# TX_FM.net
KiCad netlist of a schematic drawn in Altium Designer
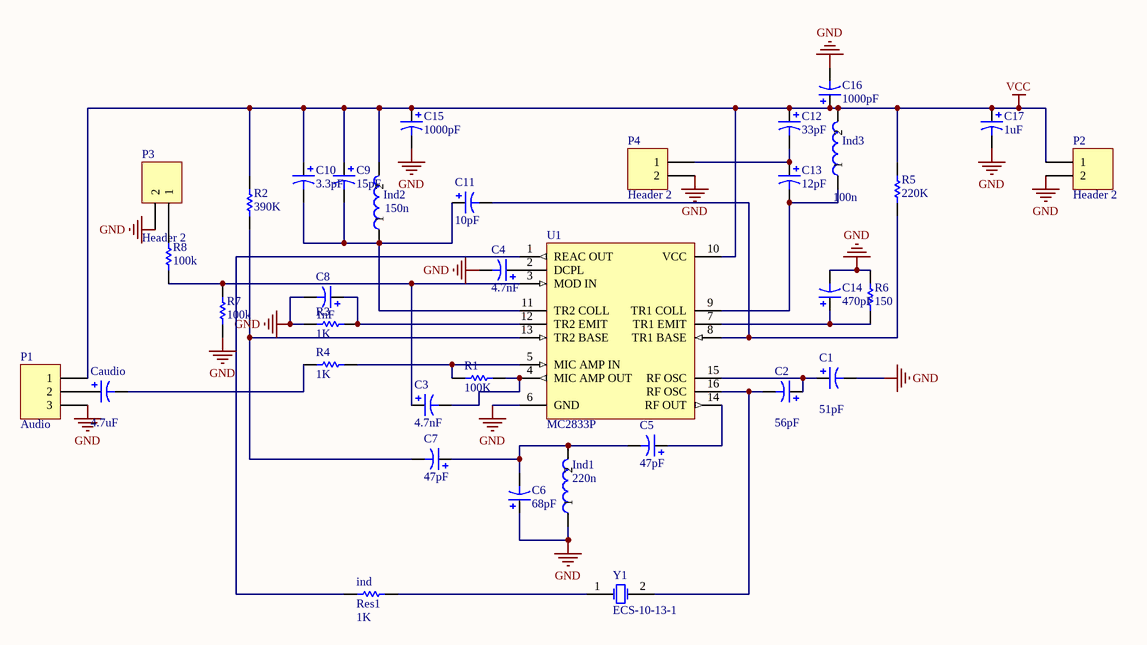
[diagram p0: TX_FM.SchDoc]

(export (version "E")
  (design (tool "Eeschema 10.0.6"))
  (components
    (comp (ref "C1")
      (value "51pF")
      (footprint "C0805")
      (description "Polarized Capacitor (Surface Mount)")
      (fields (field (name "Comment") "Cap Pol3") (field (name "PUBLISHER") "Altium Limited"))
      (libsource (lib "Miscellaneous Devices") (part "Cap Pol3"))
    )
    (comp (ref "C2")
      (value "56pF")
      (footprint "C0805")
      (description "Polarized Capacitor (Surface Mount)")
      (fields (field (name "Comment") "Cap Pol3") (field (name "PUBLISHER") "Altium Limited"))
      (libsource (lib "Miscellaneous Devices") (part "Cap Pol3"))
    )
    (comp (ref "C3")
      (value "4.7nF")
      (footprint "C0805")
      (description "Polarized Capacitor (Surface Mount)")
      (fields (field (name "Comment") "Cap Pol3") (field (name "PUBLISHER") "Altium Limited"))
      (libsource (lib "Miscellaneous Devices") (part "Cap Pol3"))
    )
    (comp (ref "C4")
      (value "4.7nF")
      (footprint "C0805")
      (description "Polarized Capacitor (Surface Mount)")
      (fields (field (name "Comment") "Cap Pol3") (field (name "PUBLISHER") "Altium Limited"))
      (libsource (lib "Miscellaneous Devices") (part "Cap Pol3"))
    )
    (comp (ref "C5")
      (value "47pF")
      (footprint "C0805")
      (description "Polarized Capacitor (Surface Mount)")
      (fields (field (name "Comment") "Cap Pol3") (field (name "PUBLISHER") "Altium Limited"))
      (libsource (lib "Miscellaneous Devices") (part "Cap Pol3"))
    )
    (comp (ref "C6")
      (value "68pF")
      (footprint "C0805")
      (description "Polarized Capacitor (Surface Mount)")
      (fields (field (name "Comment") "Cap Pol3") (field (name "PUBLISHER") "Altium Limited"))
      (libsource (lib "Miscellaneous Devices") (part "Cap Pol3"))
    )
    (comp (ref "C7")
      (value "47pF")
      (footprint "C0805")
      (description "Polarized Capacitor (Surface Mount)")
      (fields (field (name "Comment") "Cap Pol3") (field (name "PUBLISHER") "Altium Limited"))
      (libsource (lib "Miscellaneous Devices") (part "Cap Pol3"))
    )
    (comp (ref "C8")
      (value "1nF")
      (footprint "C0805")
      (description "Polarized Capacitor (Surface Mount)")
      (fields (field (name "Comment") "Cap Pol3") (field (name "PUBLISHER") "Altium Limited"))
      (libsource (lib "Miscellaneous Devices") (part "Cap Pol3"))
    )
    (comp (ref "C9")
      (value "15pF")
      (footprint "C0805")
      (description "Polarized Capacitor (Surface Mount)")
      (fields (field (name "Comment") "Cap Pol3") (field (name "PUBLISHER") "Altium Limited"))
      (libsource (lib "Miscellaneous Devices") (part "Cap Pol3"))
    )
    (comp (ref "C10")
      (value "3.3pF")
      (footprint "C0805")
      (description "Polarized Capacitor (Surface Mount)")
      (fields (field (name "Comment") "Cap Pol3") (field (name "PUBLISHER") "Altium Limited"))
      (libsource (lib "Miscellaneous Devices") (part "Cap Pol3"))
    )
    (comp (ref "C11")
      (value "10pF")
      (footprint "C0805")
      (description "Polarized Capacitor (Surface Mount)")
      (fields (field (name "Comment") "Cap Pol3") (field (name "PUBLISHER") "Altium Limited"))
      (libsource (lib "Miscellaneous Devices") (part "Cap Pol3"))
    )
    (comp (ref "C12")
      (value "33pF")
      (footprint "C0805")
      (description "Polarized Capacitor (Surface Mount)")
      (fields (field (name "Comment") "Cap Pol3") (field (name "PUBLISHER") "Altium Limited"))
      (libsource (lib "Miscellaneous Devices") (part "Cap Pol3"))
    )
    (comp (ref "C13")
      (value "12pF")
      (footprint "C0805")
      (description "Polarized Capacitor (Surface Mount)")
      (fields (field (name "Comment") "Cap Pol3") (field (name "PUBLISHER") "Altium Limited"))
      (libsource (lib "Miscellaneous Devices") (part "Cap Pol3"))
    )
    (comp (ref "C14")
      (value "470pF")
      (footprint "C0805")
      (description "Polarized Capacitor (Surface Mount)")
      (fields (field (name "Comment") "Cap Pol3") (field (name "PUBLISHER") "Altium Limited"))
      (libsource (lib "Miscellaneous Devices") (part "Cap Pol3"))
    )
    (comp (ref "C15")
      (value "1000pF")
      (footprint "C0805")
      (description "Polarized Capacitor (Surface Mount)")
      (fields (field (name "Comment") "Cap Pol3") (field (name "PUBLISHER") "Altium Limited"))
      (libsource (lib "Miscellaneous Devices") (part "Cap Pol3"))
    )
    (comp (ref "C16")
      (value "1000pF")
      (footprint "C0805")
      (description "Polarized Capacitor (Surface Mount)")
      (fields (field (name "Comment") "Cap Pol3") (field (name "PUBLISHER") "Altium Limited"))
      (libsource (lib "Miscellaneous Devices") (part "Cap Pol3"))
    )
    (comp (ref "C17")
      (value "1uF")
      (footprint "C0805")
      (description "Polarized Capacitor (Surface Mount)")
      (fields (field (name "Comment") "Cap Pol3") (field (name "PUBLISHER") "Altium Limited"))
      (libsource (lib "Miscellaneous Devices") (part "Cap Pol3"))
    )
    (comp (ref "Caudio")
      (value "4.7uF")
      (footprint "B")
      (description "Polarized Capacitor (Radial)")
      (fields (field (name "Comment") "Cap Pol1") (field (name "PUBLISHER") "Altium Limited"))
      (libsource (lib "Miscellaneous Devices") (part "Cap Pol1"))
    )
    (comp (ref "ind")
      (value "Res1")
      (footprint "AXIAL-0.3")
      (description "Resistor")
      (fields (field (name "ALTIUM_VALUE") "1K") (field (name "PUBLISHER") "Altium Limited"))
      (libsource (lib "Miscellaneous Devices") (part "Res1"))
    )
    (comp (ref "Ind1")
      (value "Ind2")
      (footprint "IND_7MM")
      (fields (field (name "VALOR") "220n"))
      (libsource (lib "epf") (part "Ind2"))
    )
    (comp (ref "Ind2")
      (value "Ind2")
      (footprint "Ind_5mm")
      (fields (field (name "VALOR") "150n"))
      (libsource (lib "epf") (part "Ind2"))
    )
    (comp (ref "Ind3")
      (value "Ind2")
      (footprint "Ind_5mm")
      (fields (field (name "VALOR") "100n"))
      (libsource (lib "epf") (part "Ind2"))
    )
    (comp (ref "P1")
      (value "Audio")
      (footprint "HDR1X3")
      (description "Header, 3-Pin")
      (fields (field (name "PUBLISHER") "Altium Limited"))
      (libsource (lib "Miscellaneous Connectors") (part "Header 3"))
    )
    (comp (ref "P2")
      (value "Header 2")
      (footprint "HDR1X2")
      (description "Header, 2-Pin")
      (fields (field (name "PUBLISHER") "Altium Limited"))
      (libsource (lib "Miscellaneous Connectors") (part "Header 2"))
    )
    (comp (ref "P3")
      (value "Header 2")
      (footprint "HDR1X2")
      (description "Header, 2-Pin")
      (fields (field (name "PUBLISHER") "Altium Limited"))
      (libsource (lib "") (part "Header 2_2"))
    )
    (comp (ref "P4")
      (value "Header 2")
      (footprint "HDR1X2")
      (description "Header, 2-Pin")
      (fields (field (name "PUBLISHER") "Altium Limited"))
      (libsource (lib "") (part "Header 2_1"))
    )
    (comp (ref "R1")
      (value "100K")
      (footprint "2012[0805]")
      (description "Semiconductor Resistor")
      (fields (field (name "Comment") "Res Semi") (field (name "PUBLISHER") "Altium Limited"))
      (libsource (lib "Miscellaneous Devices") (part "Res Semi"))
    )
    (comp (ref "R2")
      (value "390K")
      (footprint "2012[0805]")
      (description "Semiconductor Resistor")
      (fields (field (name "Comment") "Res Semi") (field (name "PUBLISHER") "Altium Limited"))
      (libsource (lib "Miscellaneous Devices") (part "Res Semi"))
    )
    (comp (ref "R3")
      (value "1K")
      (footprint "2012[0805]")
      (description "Semiconductor Resistor")
      (fields (field (name "Comment") "Res Semi") (field (name "PUBLISHER") "Altium Limited"))
      (libsource (lib "Miscellaneous Devices") (part "Res Semi"))
    )
    (comp (ref "R4")
      (value "1K")
      (footprint "2012[0805]")
      (description "Semiconductor Resistor")
      (fields (field (name "Comment") "Res Semi") (field (name "PUBLISHER") "Altium Limited"))
      (libsource (lib "Miscellaneous Devices") (part "Res Semi"))
    )
    (comp (ref "R5")
      (value "220K")
      (footprint "2012[0805]")
      (description "Semiconductor Resistor")
      (fields (field (name "Comment") "Res Semi") (field (name "PUBLISHER") "Altium Limited"))
      (libsource (lib "Miscellaneous Devices") (part "Res Semi"))
    )
    (comp (ref "R6")
      (value "150")
      (footprint "2012[0805]")
      (description "Semiconductor Resistor")
      (fields (field (name "Comment") "Res Semi") (field (name "PUBLISHER") "Altium Limited"))
      (libsource (lib "Miscellaneous Devices") (part "Res Semi"))
    )
    (comp (ref "R7")
      (value "100k")
      (footprint "2012[0805]")
      (description "Semiconductor Resistor")
      (fields (field (name "Comment") "Res Semi") (field (name "PUBLISHER") "Altium Limited"))
      (libsource (lib "Miscellaneous Devices") (part "Res Semi"))
    )
    (comp (ref "R8")
      (value "100k")
      (footprint "2012[0805]")
      (description "Semiconductor Resistor")
      (fields (field (name "Comment") "Res Semi") (field (name "PUBLISHER") "Altium Limited"))
      (libsource (lib "Miscellaneous Devices") (part "Res Semi"))
    )
    (comp (ref "U1")
      (value "MC2833P")
      (footprint "648-06")
      (description "Low Power FM Transmitter System")
      (fields (field (name "PUBLISHER") "Altium Limited"))
      (libsource (lib "Motorola RF and IF Transmitter") (part "MC2833P"))
    )
    (comp (ref "Y1")
      (value "ECS-10-13-1")
      (footprint "HC-49U")
      (description "Crystal Oscillator")
      (fields (field (name "PUBLISHER") "Altium Limited"))
      (libsource (lib "ECS Crystal Oscillator") (part "ECS-10-13-1"))
    )
  )
  (nets
    (net (code "1") (name "GND") (class "Default")
      (node (ref "C1") (pin "2") (pinfunction "2_2") (pintype "passive"))
      (node (ref "C14") (pin "2") (pinfunction "2_2") (pintype "passive"))
      (node (ref "C15") (pin "2") (pinfunction "2_2") (pintype "passive"))
      (node (ref "C16") (pin "2") (pinfunction "2_2") (pintype "passive"))
      (node (ref "C17") (pin "2") (pinfunction "2_2") (pintype "passive"))
      (node (ref "C4") (pin "2") (pinfunction "2_2") (pintype "passive"))
      (node (ref "C6") (pin "1") (pinfunction "1_1") (pintype "passive"))
      (node (ref "C8") (pin "2") (pinfunction "2_2") (pintype "passive"))
      (node (ref "Ind1") (pin "1") (pinfunction "1_1") (pintype "passive"))
      (node (ref "P1") (pin "3") (pinfunction "3_3") (pintype "passive"))
      (node (ref "P2") (pin "2") (pinfunction "2_2") (pintype "passive"))
      (node (ref "P3") (pin "2") (pinfunction "2_2") (pintype "passive"))
      (node (ref "P4") (pin "2") (pinfunction "2_2") (pintype "passive"))
      (node (ref "R3") (pin "2") (pinfunction "2_2") (pintype "passive"))
      (node (ref "R6") (pin "1") (pinfunction "1_1") (pintype "passive"))
      (node (ref "R7") (pin "2") (pinfunction "2_2") (pintype "passive"))
      (node (ref "U1") (pin "6") (pinfunction "GND_6") (pintype "power_in"))
    )
    (net (code "2") (name "Net-(C1-Pad1)") (class "Default")
      (node (ref "C1") (pin "1") (pinfunction "1_1") (pintype "passive"))
      (node (ref "C2") (pin "1") (pinfunction "1_1") (pintype "passive"))
      (node (ref "U1") (pin "15") (pinfunction "RF_OSC_15") (pintype "passive"))
    )
    (net (code "3") (name "Net-(C5-Pad2)") (class "Default")
      (node (ref "C5") (pin "2") (pinfunction "2_2") (pintype "passive"))
      (node (ref "C6") (pin "2") (pinfunction "2_2") (pintype "passive"))
      (node (ref "C7") (pin "1") (pinfunction "1_1") (pintype "passive"))
      (node (ref "Ind1") (pin "2") (pinfunction "2_2") (pintype "passive"))
    )
    (net (code "4") (name "Net-(C12-Pad2)") (class "Default")
      (node (ref "C12") (pin "2") (pinfunction "2_2") (pintype "passive"))
      (node (ref "C13") (pin "1") (pinfunction "1_1") (pintype "passive"))
      (node (ref "P4") (pin "1") (pinfunction "1_1") (pintype "passive"))
    )
    (net (code "5") (name "Net-(Caudio-Pad1)") (class "Default")
      (node (ref "Caudio") (pin "1") (pinfunction "1_1") (pintype "passive"))
      (node (ref "P1") (pin "2") (pinfunction "2_2") (pintype "passive"))
    )
    (net (code "6") (name "Net-(Caudio-Pad2)") (class "Default")
      (node (ref "Caudio") (pin "2") (pinfunction "2_2") (pintype "passive"))
      (node (ref "R4") (pin "2") (pinfunction "2_2") (pintype "passive"))
    )
    (net (code "7") (name "Net-(P3-Pad1)") (class "Default")
      (node (ref "P3") (pin "1") (pinfunction "1_1") (pintype "passive"))
      (node (ref "R8") (pin "1") (pinfunction "1_1") (pintype "passive"))
    )
    (net (code "8") (name "Net-(U1-DCPL)") (class "Default")
      (node (ref "C4") (pin "1") (pinfunction "1_1") (pintype "passive"))
      (node (ref "U1") (pin "2") (pinfunction "DCPL_2") (pintype "passive"))
    )
    (net (code "9") (name "Net-(U1-MIC_AMP_IN)") (class "Default")
      (node (ref "R1") (pin "1") (pinfunction "1_1") (pintype "passive"))
      (node (ref "R4") (pin "1") (pinfunction "1_1") (pintype "passive"))
      (node (ref "U1") (pin "5") (pinfunction "MIC_AMP_IN_5") (pintype "input"))
    )
    (net (code "10") (name "Net-(U1-MIC_AMP_OUT)") (class "Default")
      (node (ref "C3") (pin "2") (pinfunction "2_2") (pintype "passive"))
      (node (ref "R1") (pin "2") (pinfunction "2_2") (pintype "passive"))
      (node (ref "U1") (pin "4") (pinfunction "MIC_AMP_OUT_4") (pintype "output"))
    )
    (net (code "11") (name "Net-(U1-MOD_IN)") (class "Default")
      (node (ref "C3") (pin "1") (pinfunction "1_1") (pintype "passive"))
      (node (ref "R7") (pin "1") (pinfunction "1_1") (pintype "passive"))
      (node (ref "R8") (pin "2") (pinfunction "2_2") (pintype "passive"))
      (node (ref "U1") (pin "3") (pinfunction "MOD_IN_3") (pintype "input"))
    )
    (net (code "12") (name "Net-(U1-REAC_OUT)") (class "Default")
      (node (ref "U1") (pin "1") (pinfunction "REAC_OUT_1") (pintype "output"))
      (node (ref "ind") (pin "1") (pinfunction "1_1") (pintype "passive"))
    )
    (net (code "13") (name "Net-(U1-RF_OUT)") (class "Default")
      (node (ref "C5") (pin "1") (pinfunction "1_1") (pintype "passive"))
      (node (ref "U1") (pin "14") (pinfunction "RF_OUT_14") (pintype "output"))
    )
    (net (code "14") (name "Net-(U1-TR1_BASE)") (class "Default")
      (node (ref "C11") (pin "2") (pinfunction "2_2") (pintype "passive"))
      (node (ref "R5") (pin "2") (pinfunction "2_2") (pintype "passive"))
      (node (ref "U1") (pin "8") (pinfunction "TR1_BASE_8") (pintype "input"))
    )
    (net (code "15") (name "Net-(U1-TR1_COLL)") (class "Default")
      (node (ref "C13") (pin "2") (pinfunction "2_2") (pintype "passive"))
      (node (ref "Ind3") (pin "1") (pinfunction "1_1") (pintype "passive"))
      (node (ref "U1") (pin "9") (pinfunction "TR1_COLL_9") (pintype "open_collector"))
    )
    (net (code "16") (name "Net-(U1-TR1_EMIT)") (class "Default")
      (node (ref "C14") (pin "1") (pinfunction "1_1") (pintype "passive"))
      (node (ref "R6") (pin "2") (pinfunction "2_2") (pintype "passive"))
      (node (ref "U1") (pin "7") (pinfunction "TR1_EMIT_7") (pintype "open_emitter"))
    )
    (net (code "17") (name "Net-(U1-TR2_BASE)") (class "Default")
      (node (ref "C7") (pin "2") (pinfunction "2_2") (pintype "passive"))
      (node (ref "R2") (pin "1") (pinfunction "1_1") (pintype "passive"))
      (node (ref "U1") (pin "13") (pinfunction "TR2_BASE_13") (pintype "input"))
    )
    (net (code "18") (name "Net-(U1-TR2_COLL)") (class "Default")
      (node (ref "C10") (pin "2") (pinfunction "2_2") (pintype "passive"))
      (node (ref "C11") (pin "1") (pinfunction "1_1") (pintype "passive"))
      (node (ref "C9") (pin "2") (pinfunction "2_2") (pintype "passive"))
      (node (ref "Ind2") (pin "1") (pinfunction "1_1") (pintype "passive"))
      (node (ref "U1") (pin "11") (pinfunction "TR2_COLL_11") (pintype "open_collector"))
    )
    (net (code "19") (name "Net-(U1-TR2_EMIT)") (class "Default")
      (node (ref "C8") (pin "1") (pinfunction "1_1") (pintype "passive"))
      (node (ref "R3") (pin "1") (pinfunction "1_1") (pintype "passive"))
      (node (ref "U1") (pin "12") (pinfunction "TR2_EMIT_12") (pintype "open_emitter"))
    )
    (net (code "20") (name "Net-(Y1-OSC1)") (class "Default")
      (node (ref "Y1") (pin "1") (pinfunction "OSC1_1") (pintype "passive"))
      (node (ref "ind") (pin "2") (pinfunction "2_2") (pintype "passive"))
    )
    (net (code "21") (name "Net-(Y1-OSC2)") (class "Default")
      (node (ref "C2") (pin "2") (pinfunction "2_2") (pintype "passive"))
      (node (ref "U1") (pin "16") (pinfunction "RF_OSC_16") (pintype "passive"))
      (node (ref "Y1") (pin "2") (pinfunction "OSC2_2") (pintype "passive"))
    )
    (net (code "22") (name "VCC") (class "Default")
      (node (ref "C10") (pin "1") (pinfunction "1_1") (pintype "passive"))
      (node (ref "C12") (pin "1") (pinfunction "1_1") (pintype "passive"))
      (node (ref "C15") (pin "1") (pinfunction "1_1") (pintype "passive"))
      (node (ref "C16") (pin "1") (pinfunction "1_1") (pintype "passive"))
      (node (ref "C17") (pin "1") (pinfunction "1_1") (pintype "passive"))
      (node (ref "C9") (pin "1") (pinfunction "1_1") (pintype "passive"))
      (node (ref "Ind2") (pin "2") (pinfunction "2_2") (pintype "passive"))
      (node (ref "Ind3") (pin "2") (pinfunction "2_2") (pintype "passive"))
      (node (ref "P1") (pin "1") (pinfunction "1_1") (pintype "passive"))
      (node (ref "P2") (pin "1") (pinfunction "1_1") (pintype "passive"))
      (node (ref "R2") (pin "2") (pinfunction "2_2") (pintype "passive"))
      (node (ref "R5") (pin "1") (pinfunction "1_1") (pintype "passive"))
      (node (ref "U1") (pin "10") (pinfunction "VCC_10") (pintype "power_in"))
    )
  )
)
